# Switch.net
KiCad netlist of a schematic drawn in EAGLE
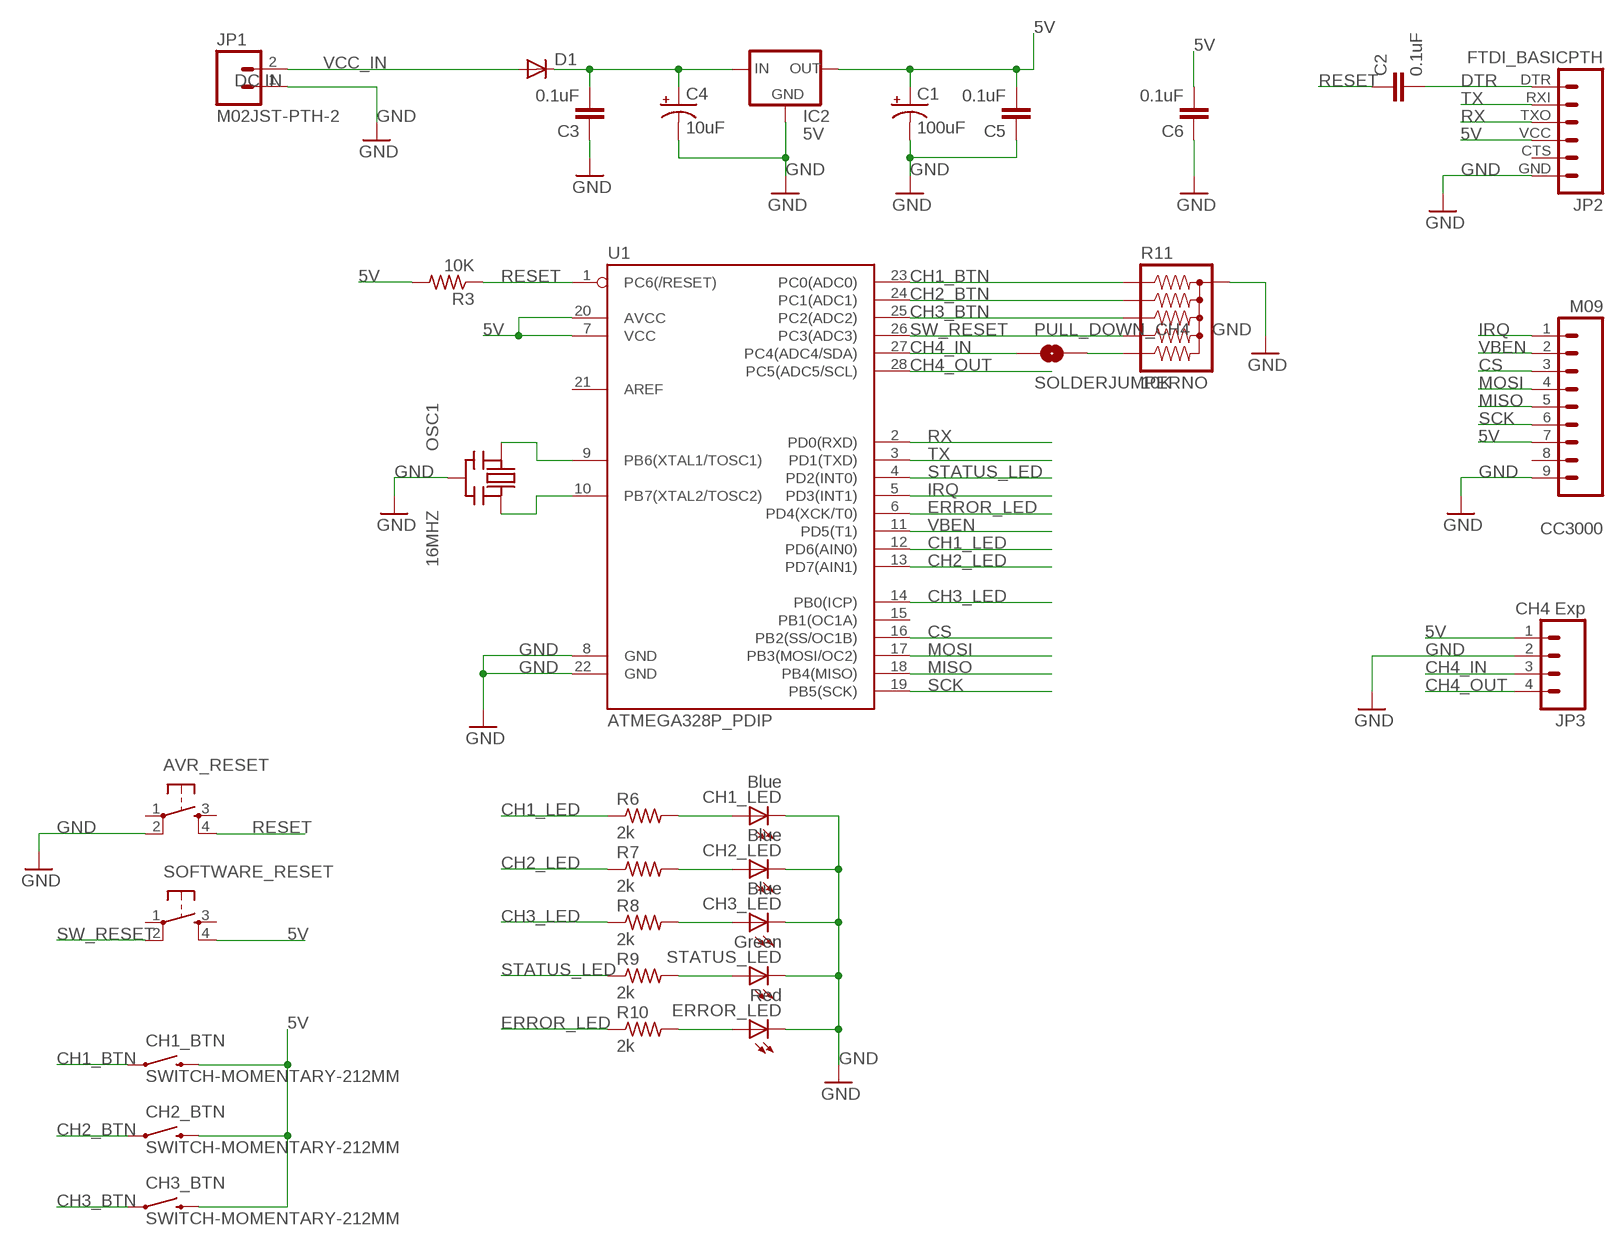
[diagram p0: schematic, sheet 1]

(export (version "E")
  (design (tool "Eeschema 10.0.6"))
  (components
    (comp (ref "AVR_RESET")
      (value "TAC_SWITCHPTH")
      (footprint "eagle-import:TACTILE-PTH")
      (libsource (lib "eagle-import") (part "TAC_SWITCHPTH"))
    )
    (comp (ref "C1")
      (value "100uF")
      (footprint "eagle-import:CPOL-RADIAL-100UF-25V")
      (libsource (lib "eagle-import") (part "CAP_POLPTH1"))
    )
    (comp (ref "C2")
      (value "0.1uF")
      (footprint "eagle-import:CAP-PTH-SMALL")
      (libsource (lib "eagle-import") (part "CAPPTH"))
    )
    (comp (ref "C3")
      (value "0.1uF")
      (footprint "eagle-import:CAP-PTH-SMALL")
      (libsource (lib "eagle-import") (part "CAPPTH"))
    )
    (comp (ref "C4")
      (value "10uF")
      (footprint "eagle-import:CPOL-RADIAL-10UF-25V")
      (libsource (lib "eagle-import") (part "CAP_POLPTH2"))
    )
    (comp (ref "C5")
      (value "0.1uF")
      (footprint "eagle-import:CAP-PTH-SMALL")
      (libsource (lib "eagle-import") (part "CAPPTH"))
    )
    (comp (ref "C6")
      (value "0.1uF")
      (footprint "eagle-import:CAP-PTH-SMALL")
      (libsource (lib "eagle-import") (part "CAPPTH"))
    )
    (comp (ref "CC3000")
      (value "M09")
      (footprint "eagle-import:1X09")
      (libsource (lib "eagle-import") (part "M09"))
    )
    (comp (ref "CH1_BTN")
      (value "SWITCH-MOMENTARY-212MM")
      (footprint "eagle-import:TACTILE-PTH-12MM")
      (libsource (lib "eagle-import") (part "SWITCH-MOMENTARY-212MM"))
    )
    (comp (ref "CH1_LED")
      (value "Blue")
      (footprint "eagle-import:LED3MM")
      (libsource (lib "eagle-import") (part "LED3MM"))
    )
    (comp (ref "CH2_BTN")
      (value "SWITCH-MOMENTARY-212MM")
      (footprint "eagle-import:TACTILE-PTH-12MM")
      (libsource (lib "eagle-import") (part "SWITCH-MOMENTARY-212MM"))
    )
    (comp (ref "CH2_LED")
      (value "Blue")
      (footprint "eagle-import:LED3MM")
      (libsource (lib "eagle-import") (part "LED3MM"))
    )
    (comp (ref "CH3_BTN")
      (value "SWITCH-MOMENTARY-212MM")
      (footprint "eagle-import:TACTILE-PTH-12MM")
      (libsource (lib "eagle-import") (part "SWITCH-MOMENTARY-212MM"))
    )
    (comp (ref "CH3_LED")
      (value "Blue")
      (footprint "eagle-import:LED3MM")
      (libsource (lib "eagle-import") (part "LED3MM"))
    )
    (comp (ref "D1")
      (value "DIODEPTH")
      (footprint "eagle-import:DIODE-1N4001")
      (libsource (lib "eagle-import") (part "DIODEPTH"))
    )
    (comp (ref "ERROR_LED")
      (value "Red")
      (footprint "eagle-import:LED3MM")
      (libsource (lib "eagle-import") (part "LED3MM"))
    )
    (comp (ref "IC2")
      (value "5V")
      (footprint "eagle-import:78XXS")
      (libsource (lib "eagle-import") (part "78XXS"))
    )
    (comp (ref "JP1")
      (value "M02JST-PTH-2")
      (footprint "eagle-import:JST-2-PTH")
      (fields (field (name "LABEL") "DC IN"))
      (libsource (lib "eagle-import") (part "M02JST-PTH-2"))
    )
    (comp (ref "JP2")
      (value "FTDI_BASICPTH")
      (footprint "eagle-import:FTDI_BASIC")
      (libsource (lib "eagle-import") (part "FTDI_BASICPTH"))
    )
    (comp (ref "JP3")
      (value "CH4 Exp")
      (footprint "eagle-import:JST-4-PTH")
      (libsource (lib "eagle-import") (part "M04JST-PTH"))
    )
    (comp (ref "OSC1")
      (value "16MHZ")
      (footprint "eagle-import:CERM_OSC")
      (libsource (lib "eagle-import") (part "CERMOSCILL-THM"))
    )
    (comp (ref "PULL_DOWN_CH4")
      (value "SOLDERJUMPERNO")
      (footprint "eagle-import:SJ_2S-NO")
      (libsource (lib "eagle-import") (part "SOLDERJUMPERNO"))
    )
    (comp (ref "R3")
      (value "10K")
      (footprint "eagle-import:0207_15")
      (libsource (lib "eagle-import") (part "R-US_0207/15"))
    )
    (comp (ref "R6")
      (value "2k")
      (footprint "eagle-import:0207_15")
      (libsource (lib "eagle-import") (part "R-US_0207/15"))
    )
    (comp (ref "R7")
      (value "2k")
      (footprint "eagle-import:0207_15")
      (libsource (lib "eagle-import") (part "R-US_0207/15"))
    )
    (comp (ref "R8")
      (value "2k")
      (footprint "eagle-import:0207_15")
      (libsource (lib "eagle-import") (part "R-US_0207/15"))
    )
    (comp (ref "R9")
      (value "2k")
      (footprint "eagle-import:0207_15")
      (libsource (lib "eagle-import") (part "R-US_0207/15"))
    )
    (comp (ref "R10")
      (value "2k")
      (footprint "eagle-import:0207_15")
      (libsource (lib "eagle-import") (part "R-US_0207/15"))
    )
    (comp (ref "R11")
      (value "10K")
      (footprint "eagle-import:RPACK-SIP-PTH-5")
      (libsource (lib "eagle-import") (part "RPACK-BUSSED-SIP-PTH-5"))
    )
    (comp (ref "SOFTWARE_RESET")
      (value "TAC_SWITCHPTH")
      (footprint "eagle-import:TACTILE-PTH")
      (libsource (lib "eagle-import") (part "TAC_SWITCHPTH"))
    )
    (comp (ref "STATUS_LED")
      (value "Green")
      (footprint "eagle-import:LED3MM")
      (libsource (lib "eagle-import") (part "LED3MM"))
    )
    (comp (ref "U1")
      (value "ATMEGA328P_PDIP")
      (footprint "eagle-import:DIL28-3")
      (libsource (lib "eagle-import") (part "ATMEGA328P_PDIP"))
    )
  )
  (nets
    (net (code "1") (name "/5V") (class "Default")
      (node (ref "C1") (pin "1") (pinfunction "+_1") (pintype "passive"))
      (node (ref "C5") (pin "2") (pinfunction "2_2") (pintype "passive"))
      (node (ref "C6") (pin "2") (pinfunction "2_2") (pintype "passive"))
      (node (ref "CC3000") (pin "7") (pinfunction "7_7") (pintype "passive"))
      (node (ref "CH1_BTN") (pin "3") (pinfunction "2_3") (pintype "passive"))
      (node (ref "CH2_BTN") (pin "3") (pinfunction "2_3") (pintype "passive"))
      (node (ref "CH3_BTN") (pin "3") (pinfunction "2_3") (pintype "passive"))
      (node (ref "IC2") (pin "OUT") (pinfunction "OUT_OUT") (pintype "passive"))
      (node (ref "JP2") (pin "VCC") (pinfunction "4_VCC") (pintype "passive"))
      (node (ref "JP3") (pin "1") (pinfunction "1_1") (pintype "passive"))
      (node (ref "R3") (pin "2") (pinfunction "2_2") (pintype "passive"))
      (node (ref "SOFTWARE_RESET") (pin "4") (pinfunction "4_4") (pintype "passive"))
      (node (ref "U1") (pin "20") (pinfunction "AVCC_20") (pintype "bidirectional"))
      (node (ref "U1") (pin "7") (pinfunction "VCC_7") (pintype "bidirectional"))
    )
    (net (code "2") (name "/CH1_BTN") (class "Default")
      (node (ref "CH1_BTN") (pin "1") (pinfunction "1_1") (pintype "passive"))
      (node (ref "R11") (pin "P$2") (pinfunction "2_P$2") (pintype "passive"))
      (node (ref "U1") (pin "23") (pinfunction "PC0(ADC0)_23") (pintype "bidirectional"))
    )
    (net (code "3") (name "/CH1_LED") (class "Default")
      (node (ref "R6") (pin "1") (pinfunction "1_1") (pintype "passive"))
      (node (ref "U1") (pin "12") (pinfunction "PD6(AIN0)_12") (pintype "bidirectional"))
    )
    (net (code "4") (name "/CH2_BTN") (class "Default")
      (node (ref "CH2_BTN") (pin "1") (pinfunction "1_1") (pintype "passive"))
      (node (ref "R11") (pin "P$3") (pinfunction "3_P$3") (pintype "passive"))
      (node (ref "U1") (pin "24") (pinfunction "PC1(ADC1)_24") (pintype "bidirectional"))
    )
    (net (code "5") (name "/CH2_LED") (class "Default")
      (node (ref "R7") (pin "1") (pinfunction "1_1") (pintype "passive"))
      (node (ref "U1") (pin "13") (pinfunction "PD7(AIN1)_13") (pintype "bidirectional"))
    )
    (net (code "6") (name "/CH3_BTN") (class "Default")
      (node (ref "CH3_BTN") (pin "1") (pinfunction "1_1") (pintype "passive"))
      (node (ref "R11") (pin "P$4") (pinfunction "4_P$4") (pintype "passive"))
      (node (ref "U1") (pin "25") (pinfunction "PC2(ADC2)_25") (pintype "bidirectional"))
    )
    (net (code "7") (name "/CH3_LED") (class "Default")
      (node (ref "R8") (pin "1") (pinfunction "1_1") (pintype "passive"))
      (node (ref "U1") (pin "14") (pinfunction "PB0(ICP)_14") (pintype "bidirectional"))
    )
    (net (code "8") (name "/CH4_IN") (class "Default")
      (node (ref "JP3") (pin "3") (pinfunction "3_3") (pintype "passive"))
      (node (ref "PULL_DOWN_CH4") (pin "1") (pinfunction "1_1") (pintype "passive"))
      (node (ref "U1") (pin "27") (pinfunction "PC4(ADC4/SDA)_27") (pintype "bidirectional"))
    )
    (net (code "9") (name "/CH4_OUT") (class "Default")
      (node (ref "JP3") (pin "4") (pinfunction "4_4") (pintype "passive"))
      (node (ref "U1") (pin "28") (pinfunction "PC5(ADC5/SCL)_28") (pintype "bidirectional"))
    )
    (net (code "10") (name "/CS") (class "Default")
      (node (ref "CC3000") (pin "3") (pinfunction "3_3") (pintype "passive"))
      (node (ref "U1") (pin "16") (pinfunction "PB2(SS/OC1B)_16") (pintype "bidirectional"))
    )
    (net (code "11") (name "/DTR") (class "Default")
      (node (ref "C2") (pin "2") (pinfunction "2_2") (pintype "passive"))
      (node (ref "JP2") (pin "DTR") (pinfunction "1_DTR") (pintype "passive"))
    )
    (net (code "12") (name "/ERROR_LED") (class "Default")
      (node (ref "R10") (pin "1") (pinfunction "1_1") (pintype "passive"))
      (node (ref "U1") (pin "6") (pinfunction "PD4(XCK/T0)_6") (pintype "bidirectional"))
    )
    (net (code "13") (name "/IRQ") (class "Default")
      (node (ref "CC3000") (pin "1") (pinfunction "1_1") (pintype "passive"))
      (node (ref "U1") (pin "5") (pinfunction "PD3(INT1)_5") (pintype "bidirectional"))
    )
    (net (code "14") (name "/MISO") (class "Default")
      (node (ref "CC3000") (pin "5") (pinfunction "5_5") (pintype "passive"))
      (node (ref "U1") (pin "18") (pinfunction "PB4(MISO)_18") (pintype "bidirectional"))
    )
    (net (code "15") (name "/MOSI") (class "Default")
      (node (ref "CC3000") (pin "4") (pinfunction "4_4") (pintype "passive"))
      (node (ref "U1") (pin "17") (pinfunction "PB3(MOSI/OC2)_17") (pintype "bidirectional"))
    )
    (net (code "16") (name "/RESET") (class "Default")
      (node (ref "AVR_RESET") (pin "4") (pinfunction "4_4") (pintype "passive"))
      (node (ref "C2") (pin "1") (pinfunction "1_1") (pintype "passive"))
      (node (ref "R3") (pin "1") (pinfunction "1_1") (pintype "passive"))
      (node (ref "U1") (pin "1") (pinfunction "PC6(/RESET)_1") (pintype "bidirectional"))
    )
    (net (code "17") (name "/RX") (class "Default")
      (node (ref "JP2") (pin "TXO") (pinfunction "3_TXO") (pintype "passive"))
      (node (ref "U1") (pin "2") (pinfunction "PD0(RXD)_2") (pintype "bidirectional"))
    )
    (net (code "18") (name "/SCK") (class "Default")
      (node (ref "CC3000") (pin "6") (pinfunction "6_6") (pintype "passive"))
      (node (ref "U1") (pin "19") (pinfunction "PB5(SCK)_19") (pintype "bidirectional"))
    )
    (net (code "19") (name "/STATUS_LED") (class "Default")
      (node (ref "R9") (pin "1") (pinfunction "1_1") (pintype "passive"))
      (node (ref "U1") (pin "4") (pinfunction "PD2(INT0)_4") (pintype "bidirectional"))
    )
    (net (code "20") (name "/SW_RESET") (class "Default")
      (node (ref "R11") (pin "P$5") (pinfunction "5_P$5") (pintype "passive"))
      (node (ref "SOFTWARE_RESET") (pin "2") (pinfunction "2_2") (pintype "passive"))
      (node (ref "U1") (pin "26") (pinfunction "PC3(ADC3)_26") (pintype "bidirectional"))
    )
    (net (code "21") (name "/TX") (class "Default")
      (node (ref "JP2") (pin "RXI") (pinfunction "2_RXI") (pintype "passive"))
      (node (ref "U1") (pin "3") (pinfunction "PD1(TXD)_3") (pintype "bidirectional"))
    )
    (net (code "22") (name "/VBEN") (class "Default")
      (node (ref "CC3000") (pin "2") (pinfunction "2_2") (pintype "passive"))
      (node (ref "U1") (pin "11") (pinfunction "PD5(T1)_11") (pintype "bidirectional"))
    )
    (net (code "23") (name "/VCC_IN") (class "Default")
      (node (ref "D1") (pin "A") (pinfunction "A_A") (pintype "passive"))
      (node (ref "JP1") (pin "2") (pinfunction "2_2") (pintype "passive"))
    )
    (net (code "24") (name "GND") (class "Default")
      (node (ref "AVR_RESET") (pin "2") (pinfunction "2_2") (pintype "passive"))
      (node (ref "C1") (pin "2") (pinfunction "-_2") (pintype "passive"))
      (node (ref "C3") (pin "1") (pinfunction "1_1") (pintype "passive"))
      (node (ref "C4") (pin "2") (pinfunction "-_2") (pintype "passive"))
      (node (ref "C5") (pin "1") (pinfunction "1_1") (pintype "passive"))
      (node (ref "C6") (pin "1") (pinfunction "1_1") (pintype "passive"))
      (node (ref "CC3000") (pin "9") (pinfunction "9_9") (pintype "passive"))
      (node (ref "CH1_LED") (pin "K") (pinfunction "C_K") (pintype "passive"))
      (node (ref "CH2_LED") (pin "K") (pinfunction "C_K") (pintype "passive"))
      (node (ref "CH3_LED") (pin "K") (pinfunction "C_K") (pintype "passive"))
      (node (ref "ERROR_LED") (pin "K") (pinfunction "C_K") (pintype "passive"))
      (node (ref "IC2") (pin "GND") (pinfunction "GND_GND") (pintype "input"))
      (node (ref "JP1") (pin "1") (pinfunction "1_1") (pintype "passive"))
      (node (ref "JP2") (pin "GND") (pinfunction "6_GND") (pintype "passive"))
      (node (ref "JP3") (pin "2") (pinfunction "2_2") (pintype "passive"))
      (node (ref "OSC1") (pin "P$2") (pinfunction "GND_P$2") (pintype "bidirectional"))
      (node (ref "R11") (pin "P$1") (pinfunction "1_P$1") (pintype "passive"))
      (node (ref "STATUS_LED") (pin "K") (pinfunction "C_K") (pintype "passive"))
      (node (ref "U1") (pin "22") (pinfunction "GND_22") (pintype "bidirectional"))
      (node (ref "U1") (pin "8") (pinfunction "GND_8") (pintype "bidirectional"))
    )
    (net (code "25") (name "Net-(C4-+)") (class "Default")
      (node (ref "C3") (pin "2") (pinfunction "2_2") (pintype "passive"))
      (node (ref "C4") (pin "1") (pinfunction "+_1") (pintype "passive"))
      (node (ref "D1") (pin "C") (pinfunction "C_C") (pintype "passive"))
      (node (ref "IC2") (pin "IN") (pinfunction "IN_IN") (pintype "input"))
    )
    (net (code "26") (name "Net-(CH1_LED-PadA)") (class "Default")
      (node (ref "CH1_LED") (pin "A") (pinfunction "A_A") (pintype "passive"))
      (node (ref "R6") (pin "2") (pinfunction "2_2") (pintype "passive"))
    )
    (net (code "27") (name "Net-(CH2_LED-PadA)") (class "Default")
      (node (ref "CH2_LED") (pin "A") (pinfunction "A_A") (pintype "passive"))
      (node (ref "R7") (pin "2") (pinfunction "2_2") (pintype "passive"))
    )
    (net (code "28") (name "Net-(CH3_LED-PadA)") (class "Default")
      (node (ref "CH3_LED") (pin "A") (pinfunction "A_A") (pintype "passive"))
      (node (ref "R8") (pin "2") (pinfunction "2_2") (pintype "passive"))
    )
    (net (code "29") (name "Net-(ERROR_LED-PadA)") (class "Default")
      (node (ref "ERROR_LED") (pin "A") (pinfunction "A_A") (pintype "passive"))
      (node (ref "R10") (pin "2") (pinfunction "2_2") (pintype "passive"))
    )
    (net (code "30") (name "Net-(OSC1-IN)") (class "Default")
      (node (ref "OSC1") (pin "P$1") (pinfunction "IN_P$1") (pintype "bidirectional"))
      (node (ref "U1") (pin "9") (pinfunction "PB6(XTAL1/TOSC1)_9") (pintype "bidirectional"))
    )
    (net (code "31") (name "Net-(OSC1-OUT)") (class "Default")
      (node (ref "OSC1") (pin "P$3") (pinfunction "OUT_P$3") (pintype "bidirectional"))
      (node (ref "U1") (pin "10") (pinfunction "PB7(XTAL2/TOSC2)_10") (pintype "bidirectional"))
    )
    (net (code "32") (name "Net-(R9-Pad2)") (class "Default")
      (node (ref "R9") (pin "2") (pinfunction "2_2") (pintype "passive"))
      (node (ref "STATUS_LED") (pin "A") (pinfunction "A_A") (pintype "passive"))
    )
    (net (code "33") (name "Net-(R11-6)") (class "Default")
      (node (ref "PULL_DOWN_CH4") (pin "2") (pinfunction "2_2") (pintype "passive"))
      (node (ref "R11") (pin "P$6") (pinfunction "6_P$6") (pintype "passive"))
    )
    (net (code "34") (name "unconnected-(AVR_RESET-Pad1)") (class "Default")
      (node (ref "AVR_RESET") (pin "1") (pinfunction "1_1") (pintype "passive"))
    )
    (net (code "35") (name "unconnected-(AVR_RESET-Pad3)") (class "Default")
      (node (ref "AVR_RESET") (pin "3") (pinfunction "3_3") (pintype "passive"))
    )
    (net (code "36") (name "unconnected-(CC3000-Pad8)") (class "Default")
      (node (ref "CC3000") (pin "8") (pinfunction "8_8") (pintype "passive"))
    )
    (net (code "37") (name "unconnected-(JP2-5-PadCTS)") (class "Default")
      (node (ref "JP2") (pin "CTS") (pinfunction "5_CTS") (pintype "passive"))
    )
    (net (code "38") (name "unconnected-(SOFTWARE_RESET-Pad1)") (class "Default")
      (node (ref "SOFTWARE_RESET") (pin "1") (pinfunction "1_1") (pintype "passive"))
    )
    (net (code "39") (name "unconnected-(SOFTWARE_RESET-Pad3)") (class "Default")
      (node (ref "SOFTWARE_RESET") (pin "3") (pinfunction "3_3") (pintype "passive"))
    )
    (net (code "40") (name "unconnected-(U1-AREF-Pad21)") (class "Default")
      (node (ref "U1") (pin "21") (pinfunction "AREF_21") (pintype "bidirectional"))
    )
    (net (code "41") (name "unconnected-(U1-PB1(OC1A)-Pad15)") (class "Default")
      (node (ref "U1") (pin "15") (pinfunction "PB1(OC1A)_15") (pintype "bidirectional"))
    )
  )
)
